# 1-Schematic_ISM_WAVER_V2.net
KiCad netlist of a schematic drawn in EasyEDA
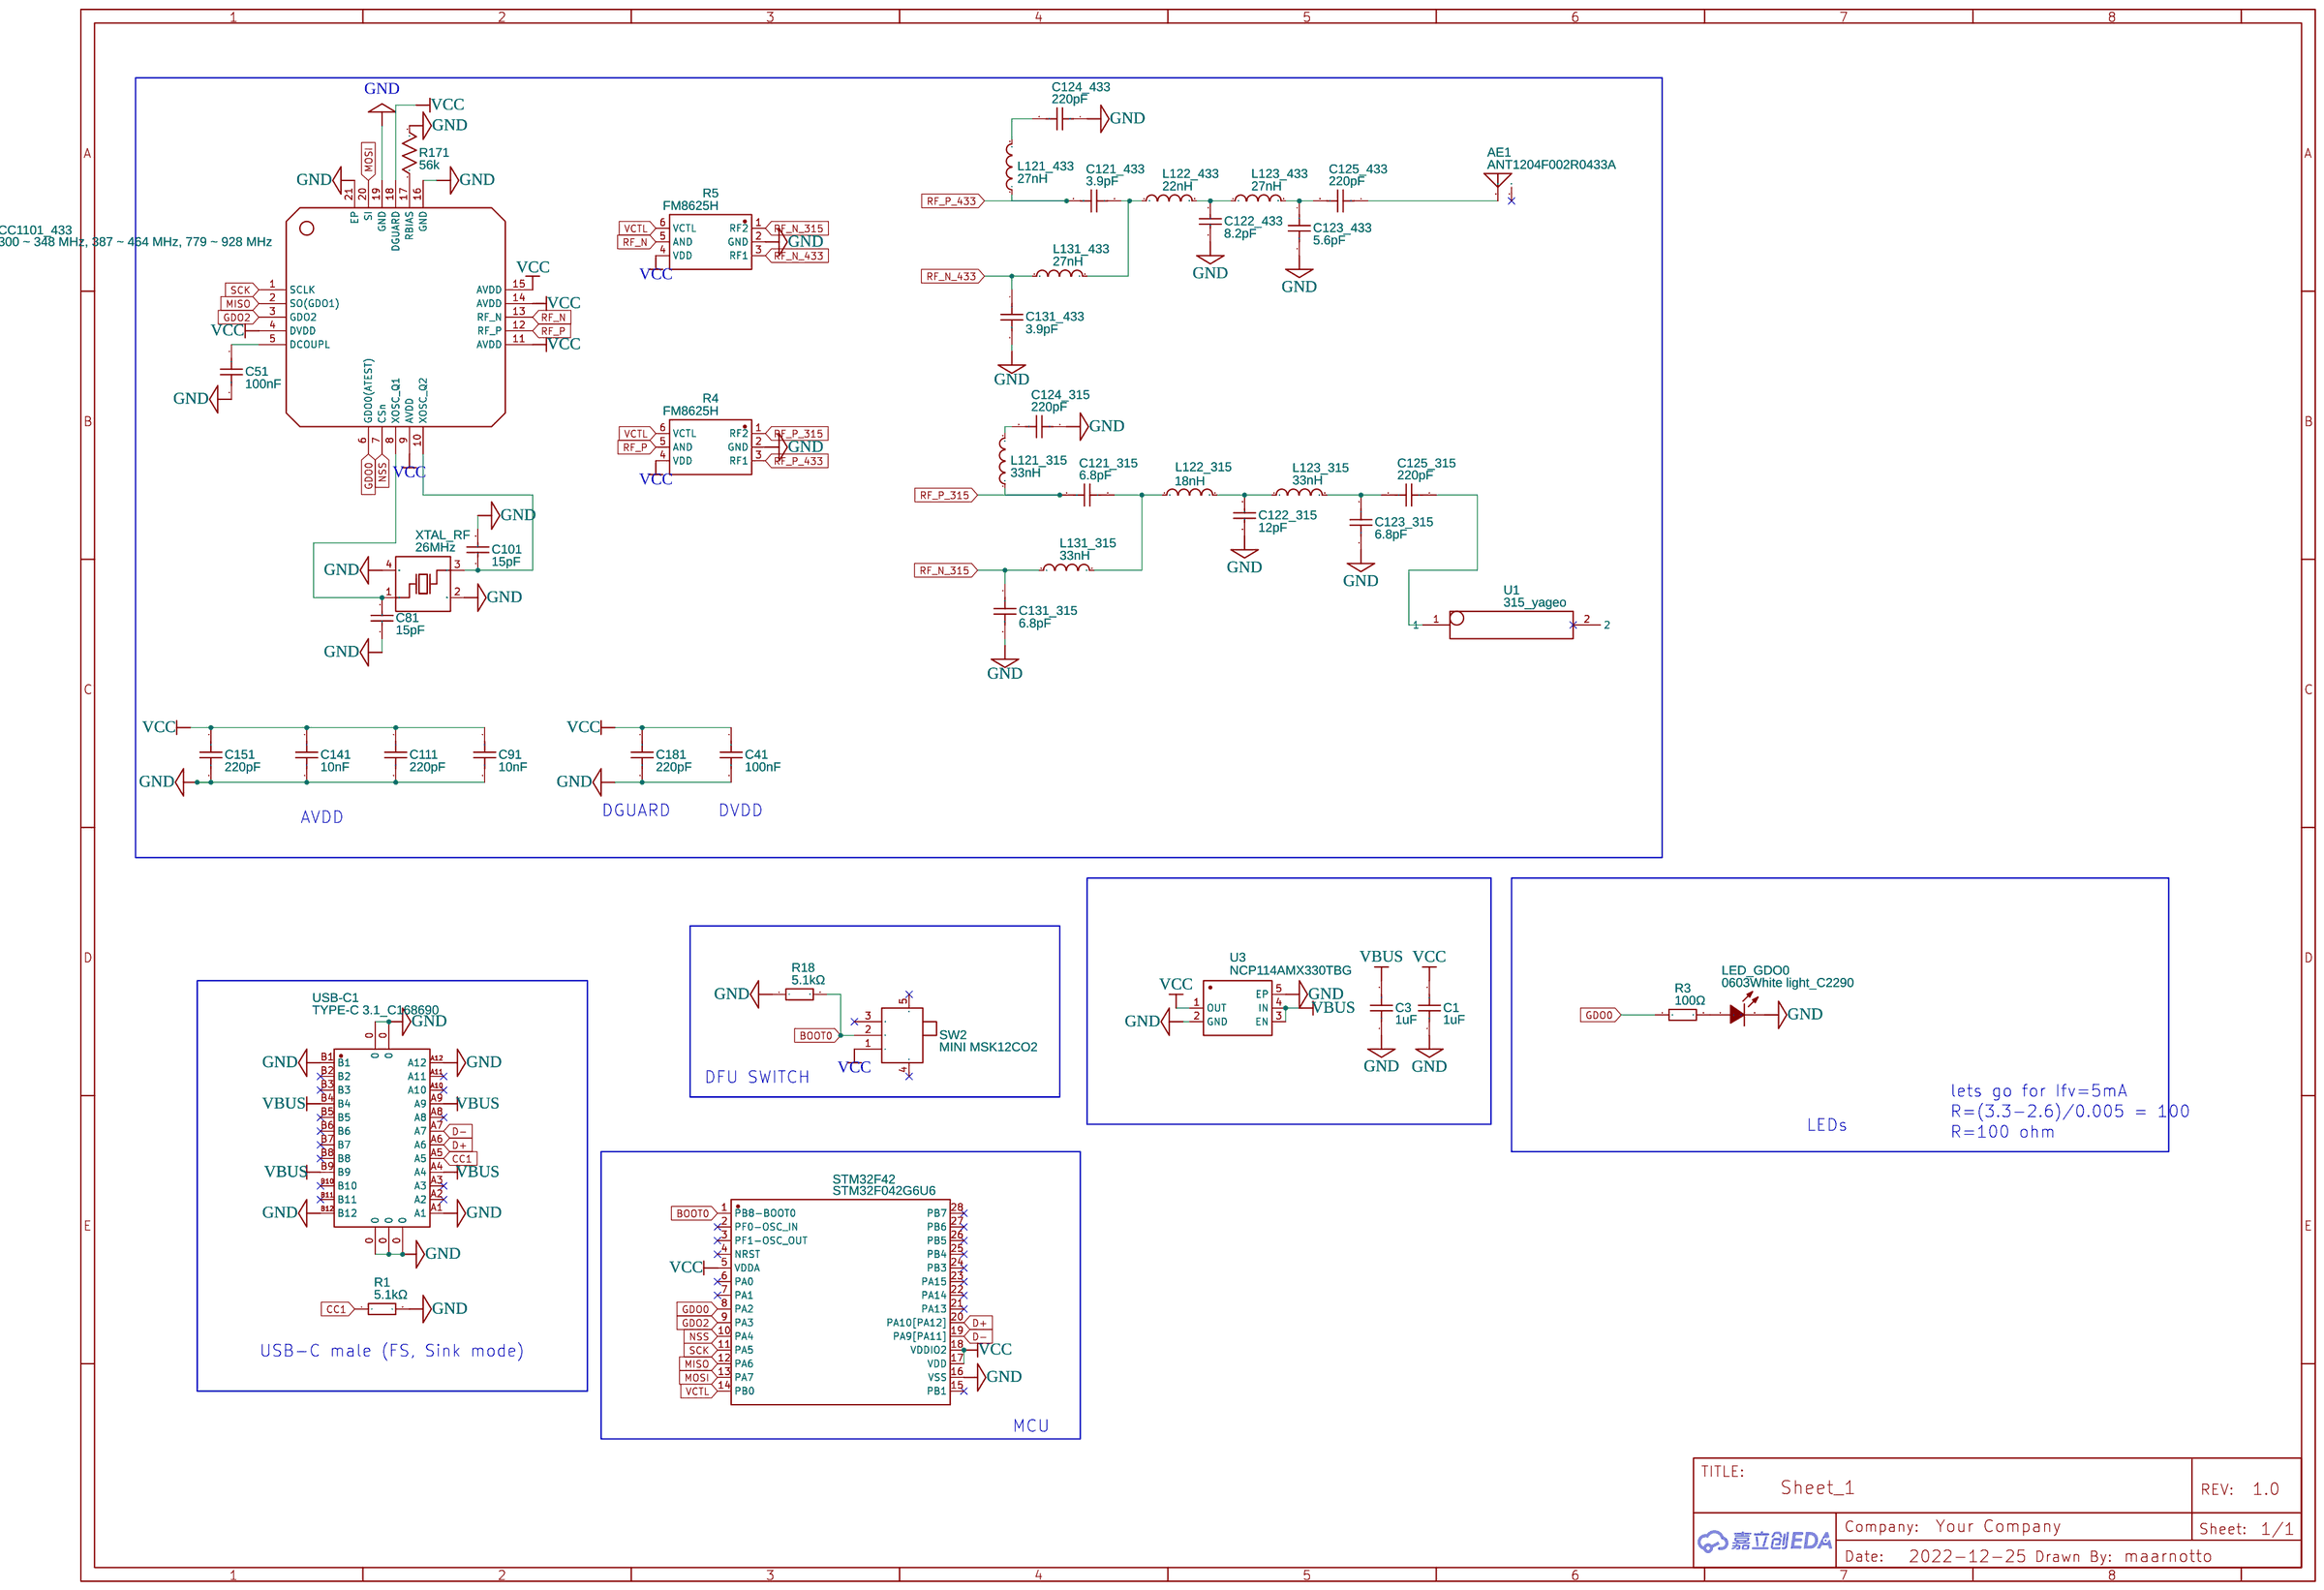
[diagram p0: schematic sheet]

(export (version "E")
  (design (tool "Eeschema 10.0.6"))
  (components
    (comp (ref "AE1")
      (value "ANT1204F002R0433A")
      (fields (field (name "Manufacturer") "YAGEO(国巨)"))
      (libsource (lib "") (part "ANT1204F002R0433A"))
    )
    (comp (ref "C1") (value "1uF") (libsource (lib "") (part "C_0603_US")))
    (comp (ref "C3") (value "1uF") (libsource (lib "") (part "C_0603_US")))
    (comp (ref "C41") (value "100nF") (libsource (lib "") (part "C_0402_US")))
    (comp (ref "C51") (value "100nF") (libsource (lib "") (part "C_0402_US")))
    (comp (ref "C81")
      (value "15pF")
      (fields (field (name "Manufacturer Part") "0402CG150J500NT") (field (name "Manufacturer") "FH(风华)"))
      (libsource (lib "") (part "0402CG150J500NT"))
    )
    (comp (ref "C91") (value "10nF") (libsource (lib "") (part "C_0402_US")))
    (comp (ref "C101")
      (value "15pF")
      (fields (field (name "Manufacturer Part") "0402CG150J500NT") (field (name "Manufacturer") "FH(风华)"))
      (libsource (lib "") (part "0402CG150J500NT"))
    )
    (comp (ref "C111") (value "220pF") (libsource (lib "") (part "C_0402_US")))
    (comp (ref "C121_315") (value "6.8pF") (libsource (lib "") (part "C_0402_US_4")))
    (comp (ref "C121_433") (value "3.9pF") (libsource (lib "") (part "C_0402_US_4")))
    (comp (ref "C122_315")
      (value "12pF")
      (fields (field (name "Manufacturer Part") "0402CG8R2C500NT") (field (name "Manufacturer") "FH(风华)"))
      (libsource (lib "") (part "0402CG8R2C500NT"))
    )
    (comp (ref "C122_433")
      (value "8.2pF")
      (fields (field (name "Manufacturer Part") "0402CG8R2C500NT") (field (name "Manufacturer") "FH(风华)"))
      (libsource (lib "") (part "0402CG8R2C500NT"))
    )
    (comp (ref "C123_315") (value "6.8pF") (libsource (lib "") (part "C_0402_US_2")))
    (comp (ref "C123_433") (value "5.6pF") (libsource (lib "") (part "C_0402_US_2")))
    (comp (ref "C124_315") (value "220pF") (libsource (lib "") (part "C_0402_US_5")))
    (comp (ref "C124_433") (value "220pF") (libsource (lib "") (part "C_0402_US_5")))
    (comp (ref "C125_315") (value "220pF") (libsource (lib "") (part "C_0402_US_3")))
    (comp (ref "C125_433") (value "220pF") (libsource (lib "") (part "C_0402_US_3")))
    (comp (ref "C131_315") (value "6.8pF") (libsource (lib "") (part "C_0402_US_1")))
    (comp (ref "C131_433") (value "3.9pF") (libsource (lib "") (part "C_0402_US_1")))
    (comp (ref "C141") (value "10nF") (libsource (lib "") (part "C_0402_US")))
    (comp (ref "C151") (value "220pF") (libsource (lib "") (part "C_0402_US")))
    (comp (ref "C181") (value "220pF") (libsource (lib "") (part "C_0402_US")))
    (comp (ref "CC1101_433")
      (value "300 ~ 348 MHz, 387 ~ 464 MHz, 779 ~ 928 MHz")
      (fields (field (name "Manufacturer Part") "CC1101RGPR") (field (name "Manufacturer") "TI(德州仪器)"))
      (libsource (lib "") (part "CC1101RGPR"))
    )
    (comp (ref "L121_315") (value "33nH") (libsource (lib "") (part "L0402_US_2")))
    (comp (ref "L121_433") (value "27nH") (libsource (lib "") (part "L0402_US_2")))
    (comp (ref "L122_315") (value "18nH") (libsource (lib "") (part "L0402_US_3")))
    (comp (ref "L122_433") (value "22nH") (libsource (lib "") (part "L0402_US_3")))
    (comp (ref "L123_315") (value "33nH") (libsource (lib "") (part "L0402_US_1")))
    (comp (ref "L123_433") (value "27nH") (libsource (lib "") (part "L0402_US_1")))
    (comp (ref "L131_315") (value "33nH") (libsource (lib "") (part "L0402_US")))
    (comp (ref "L131_433") (value "27nH") (libsource (lib "") (part "L0402_US")))
    (comp (ref "LED_GDO0")
      (value "0603White light_C2290")
      (fields (field (name "Manufacturer Part") "KT-0603白灯") (field (name "Manufacturer") "KENTO"))
      (libsource (lib "") (part "0603White light_C2290"))
    )
    (comp (ref "R1")
      (value "5.1kΩ")
      (fields
        (field (name "Manufacturer Part") "0402WGF5101TCE")
        (field (name "Manufacturer") "UNI-ROYAL(厚声)")
      )
      (libsource (lib "") (part "0402WGF5101TCE"))
    )
    (comp (ref "R3")
      (value "100Ω")
      (fields
        (field (name "Manufacturer Part") "0603WAF1000T5E")
        (field (name "Manufacturer") "UNI-ROYAL(厚声)")
      )
      (libsource (lib "") (part "0603WAF1000T5E"))
    )
    (comp (ref "R4")
      (value "FM8625H")
      (fields (field (name "Manufacturer") "FM(富满)"))
      (libsource (lib "") (part "FM8625H"))
    )
    (comp (ref "R5")
      (value "FM8625H")
      (fields (field (name "Manufacturer") "FM(富满)"))
      (libsource (lib "") (part "FM8625H"))
    )
    (comp (ref "R18")
      (value "5.1kΩ")
      (fields
        (field (name "Manufacturer Part") "0402WGF5101TCE")
        (field (name "Manufacturer") "UNI-ROYAL(厚声)")
      )
      (libsource (lib "") (part "0402WGF5101TCE"))
    )
    (comp (ref "R171") (value "56k") (libsource (lib "") (part "R_0402_US")))
    (comp (ref "STM32F42")
      (value "STM32F042G6U6")
      (fields (field (name "Manufacturer") "ST(意法半导体)"))
      (libsource (lib "") (part "STM32F042G6U6"))
    )
    (comp (ref "SW2")
      (value "MINI MSK12CO2")
      (fields (field (name "Manufacturer") "SHOU HAN(首韩)"))
      (libsource (lib "") (part "MINI MSK12CO2"))
    )
    (comp (ref "U1")
      (value "315_yageo")
      (fields
        (field (name "Manufacturer Part") "ANT1204F002R0315A")
        (field (name "Manufacturer") "PULSE ELECTRONICS")
      )
      (libsource (lib "") (part "315_yageo"))
    )
    (comp (ref "U3")
      (value "NCP114AMX330TBG")
      (fields (field (name "Manufacturer") "onsemi(安森美)"))
      (libsource (lib "") (part "NCP114AMX330TBG"))
    )
    (comp (ref "USB-C1")
      (value "TYPE-C 3.1_C168690")
      (fields (field (name "Manufacturer Part") "918-118A2021Y40000") (field (name "Manufacturer") "精拓金"))
      (libsource (lib "") (part "TYPE-C 3.1_C168690"))
    )
    (comp (ref "XTAL_RF")
      (value "26MHz")
      (fields (field (name "Manufacturer Part") "TAXM26M4RDBCCT2T") (field (name "Manufacturer") "YJX(雅晶鑫)"))
      (libsource (lib "") (part "SMD-3225_4P26MHZ10PF10PPM-40&#126;+85℃"))
    )
  )
  (nets
    (net (code "1") (name "BOOT0") (class "Default")
      (node (ref "R18") (pin "2") (pinfunction "2_2") (pintype "input"))
      (node (ref "STM32F42") (pin "1") (pinfunction "PB8-BOOT0_1") (pintype "unspecified"))
      (node (ref "SW2") (pin "2") (pinfunction "2_2") (pintype "unspecified"))
    )
    (net (code "2") (name "CC1") (class "Default")
      (node (ref "R1") (pin "1") (pinfunction "1_1") (pintype "input"))
      (node (ref "USB-C1") (pin "A5") (pinfunction "A5_A5") (pintype "unspecified"))
    )
    (net (code "3") (name "D+") (class "Default")
      (node (ref "STM32F42") (pin "20") (pinfunction "PA10[PA12]_20") (pintype "unspecified"))
      (node (ref "USB-C1") (pin "A6") (pinfunction "A6_A6") (pintype "unspecified"))
    )
    (net (code "4") (name "D-") (class "Default")
      (node (ref "STM32F42") (pin "19") (pinfunction "PA9[PA11]_19") (pintype "unspecified"))
      (node (ref "USB-C1") (pin "A7") (pinfunction "A7_A7") (pintype "unspecified"))
    )
    (net (code "5") (name "GDO0") (class "Default")
      (node (ref "CC1101_433") (pin "6") (pinfunction "GDO0(ATEST)_6") (pintype "unspecified"))
      (node (ref "R3") (pin "1") (pinfunction "1_1") (pintype "input"))
      (node (ref "STM32F42") (pin "8") (pinfunction "PA2_8") (pintype "unspecified"))
    )
    (net (code "6") (name "GDO2") (class "Default")
      (node (ref "CC1101_433") (pin "3") (pinfunction "GDO2_3") (pintype "unspecified"))
      (node (ref "STM32F42") (pin "9") (pinfunction "PA3_9") (pintype "unspecified"))
    )
    (net (code "7") (name "GND") (class "Default")
      (node (ref "C1") (pin "1") (pinfunction "1_1") (pintype "unspecified"))
      (node (ref "C101") (pin "2") (pinfunction "2_2") (pintype "input"))
      (node (ref "C111") (pin "2") (pinfunction "2_2") (pintype "unspecified"))
      (node (ref "C122_315") (pin "1") (pinfunction "1_1") (pintype "input"))
      (node (ref "C122_433") (pin "1") (pinfunction "1_1") (pintype "input"))
      (node (ref "C123_315") (pin "2") (pinfunction "2_2") (pintype "unspecified"))
      (node (ref "C123_433") (pin "2") (pinfunction "2_2") (pintype "unspecified"))
      (node (ref "C124_315") (pin "1") (pinfunction "1_1") (pintype "unspecified"))
      (node (ref "C124_433") (pin "1") (pinfunction "1_1") (pintype "unspecified"))
      (node (ref "C131_315") (pin "2") (pinfunction "2_2") (pintype "unspecified"))
      (node (ref "C131_433") (pin "2") (pinfunction "2_2") (pintype "unspecified"))
      (node (ref "C141") (pin "2") (pinfunction "2_2") (pintype "unspecified"))
      (node (ref "C151") (pin "2") (pinfunction "2_2") (pintype "unspecified"))
      (node (ref "C181") (pin "2") (pinfunction "2_2") (pintype "unspecified"))
      (node (ref "C3") (pin "1") (pinfunction "1_1") (pintype "unspecified"))
      (node (ref "C41") (pin "2") (pinfunction "2_2") (pintype "unspecified"))
      (node (ref "C51") (pin "2") (pinfunction "2_2") (pintype "unspecified"))
      (node (ref "C81") (pin "1") (pinfunction "1_1") (pintype "input"))
      (node (ref "C91") (pin "2") (pinfunction "2_2") (pintype "unspecified"))
      (node (ref "CC1101_433") (pin "16") (pinfunction "GND_16") (pintype "unspecified"))
      (node (ref "CC1101_433") (pin "19") (pinfunction "GND_19") (pintype "unspecified"))
      (node (ref "CC1101_433") (pin "21") (pinfunction "EP_21") (pintype "unspecified"))
      (node (ref "LED_GDO0") (pin "2") (pinfunction "K_2") (pintype "unspecified"))
      (node (ref "R1") (pin "2") (pinfunction "2_2") (pintype "input"))
      (node (ref "R171") (pin "2") (pinfunction "2_2") (pintype "unspecified"))
      (node (ref "R18") (pin "1") (pinfunction "1_1") (pintype "input"))
      (node (ref "R4") (pin "2") (pinfunction "GND_2") (pintype "unspecified"))
      (node (ref "R5") (pin "2") (pinfunction "GND_2") (pintype "unspecified"))
      (node (ref "STM32F42") (pin "16") (pinfunction "VSS_16") (pintype "unspecified"))
      (node (ref "U3") (pin "2") (pinfunction "GND_2") (pintype "unspecified"))
      (node (ref "U3") (pin "5") (pinfunction "EP_5") (pintype "unspecified"))
      (node (ref "USB-C1") (pin "0") (pinfunction "0_0") (pintype "unspecified"))
      (node (ref "USB-C1") (pin "A1") (pinfunction "A1_A1") (pintype "unspecified"))
      (node (ref "USB-C1") (pin "A12") (pinfunction "A12_A12") (pintype "unspecified"))
      (node (ref "USB-C1") (pin "B1") (pinfunction "B1_B1") (pintype "unspecified"))
      (node (ref "USB-C1") (pin "B12") (pinfunction "B12_B12") (pintype "unspecified"))
      (node (ref "XTAL_RF") (pin "2") (pinfunction "GND_2") (pintype "unspecified"))
      (node (ref "XTAL_RF") (pin "4") (pinfunction "GND_4") (pintype "unspecified"))
    )
    (net (code "8") (name "MISO") (class "Default")
      (node (ref "CC1101_433") (pin "2") (pinfunction "SO(GDO1)_2") (pintype "unspecified"))
      (node (ref "STM32F42") (pin "12") (pinfunction "PA6_12") (pintype "unspecified"))
    )
    (net (code "9") (name "MOSI") (class "Default")
      (node (ref "CC1101_433") (pin "20") (pinfunction "SI_20") (pintype "unspecified"))
      (node (ref "STM32F42") (pin "13") (pinfunction "PA7_13") (pintype "unspecified"))
    )
    (net (code "10") (name "NSS") (class "Default")
      (node (ref "CC1101_433") (pin "7") (pinfunction "CSn_7") (pintype "unspecified"))
      (node (ref "STM32F42") (pin "10") (pinfunction "PA4_10") (pintype "unspecified"))
    )
    (net (code "11") (name "Net-(AE1-PadS1)") (class "Default")
      (node (ref "AE1") (pin "S1") (pinfunction "S1_S1") (pintype "unspecified"))
      (node (ref "C125_433") (pin "1") (pinfunction "1_1") (pintype "unspecified"))
    )
    (net (code "12") (name "Net-(C121_315-Pad1)") (class "Default")
      (node (ref "C121_315") (pin "1") (pinfunction "1_1") (pintype "unspecified"))
      (node (ref "L122_315") (pin "1") (pinfunction "1_1") (pintype "unspecified"))
      (node (ref "L131_315") (pin "2") (pinfunction "2_2") (pintype "unspecified"))
    )
    (net (code "13") (name "Net-(C121_433-Pad1)") (class "Default")
      (node (ref "C121_433") (pin "1") (pinfunction "1_1") (pintype "unspecified"))
      (node (ref "L122_433") (pin "1") (pinfunction "1_1") (pintype "unspecified"))
      (node (ref "L131_433") (pin "2") (pinfunction "2_2") (pintype "unspecified"))
    )
    (net (code "14") (name "Net-(C122_315-Pad2)") (class "Default")
      (node (ref "C122_315") (pin "2") (pinfunction "2_2") (pintype "input"))
      (node (ref "L122_315") (pin "2") (pinfunction "2_2") (pintype "unspecified"))
      (node (ref "L123_315") (pin "1") (pinfunction "1_1") (pintype "unspecified"))
    )
    (net (code "15") (name "Net-(C122_433-Pad2)") (class "Default")
      (node (ref "C122_433") (pin "2") (pinfunction "2_2") (pintype "input"))
      (node (ref "L122_433") (pin "2") (pinfunction "2_2") (pintype "unspecified"))
      (node (ref "L123_433") (pin "1") (pinfunction "1_1") (pintype "unspecified"))
    )
    (net (code "16") (name "Net-(C123_315-Pad1)") (class "Default")
      (node (ref "C123_315") (pin "1") (pinfunction "1_1") (pintype "unspecified"))
      (node (ref "C125_315") (pin "2") (pinfunction "2_2") (pintype "unspecified"))
      (node (ref "L123_315") (pin "2") (pinfunction "2_2") (pintype "unspecified"))
    )
    (net (code "17") (name "Net-(C123_433-Pad1)") (class "Default")
      (node (ref "C123_433") (pin "1") (pinfunction "1_1") (pintype "unspecified"))
      (node (ref "C125_433") (pin "2") (pinfunction "2_2") (pintype "unspecified"))
      (node (ref "L123_433") (pin "2") (pinfunction "2_2") (pintype "unspecified"))
    )
    (net (code "18") (name "Net-(C124_315-Pad2)") (class "Default")
      (node (ref "C124_315") (pin "2") (pinfunction "2_2") (pintype "unspecified"))
      (node (ref "L121_315") (pin "2") (pinfunction "2_2") (pintype "unspecified"))
    )
    (net (code "19") (name "Net-(C124_433-Pad2)") (class "Default")
      (node (ref "C124_433") (pin "2") (pinfunction "2_2") (pintype "unspecified"))
      (node (ref "L121_433") (pin "2") (pinfunction "2_2") (pintype "unspecified"))
    )
    (net (code "20") (name "Net-(C125_315-Pad1)") (class "Default")
      (node (ref "C125_315") (pin "1") (pinfunction "1_1") (pintype "unspecified"))
      (node (ref "U1") (pin "1") (pinfunction "1_1") (pintype "unspecified"))
    )
    (net (code "21") (name "Net-(CC1101_433-DCOUPL)") (class "Default")
      (node (ref "C51") (pin "1") (pinfunction "1_1") (pintype "unspecified"))
      (node (ref "CC1101_433") (pin "5") (pinfunction "DCOUPL_5") (pintype "unspecified"))
    )
    (net (code "22") (name "Net-(CC1101_433-RBIAS)") (class "Default")
      (node (ref "CC1101_433") (pin "17") (pinfunction "RBIAS_17") (pintype "unspecified"))
      (node (ref "R171") (pin "1") (pinfunction "1_1") (pintype "unspecified"))
    )
    (net (code "23") (name "Net-(CC1101_433-XOSC_Q1)") (class "Default")
      (node (ref "C81") (pin "2") (pinfunction "2_2") (pintype "input"))
      (node (ref "CC1101_433") (pin "8") (pinfunction "XOSC_Q1_8") (pintype "unspecified"))
      (node (ref "XTAL_RF") (pin "1") (pinfunction "OSC1_1") (pintype "unspecified"))
    )
    (net (code "24") (name "Net-(CC1101_433-XOSC_Q2)") (class "Default")
      (node (ref "C101") (pin "1") (pinfunction "1_1") (pintype "input"))
      (node (ref "CC1101_433") (pin "10") (pinfunction "XOSC_Q2_10") (pintype "unspecified"))
      (node (ref "XTAL_RF") (pin "3") (pinfunction "OSC2_3") (pintype "unspecified"))
    )
    (net (code "25") (name "Net-(LED_GDO0-A)") (class "Default")
      (node (ref "LED_GDO0") (pin "1") (pinfunction "A_1") (pintype "unspecified"))
      (node (ref "R3") (pin "2") (pinfunction "2_2") (pintype "input"))
    )
    (net (code "26") (name "RF_N") (class "Default")
      (node (ref "CC1101_433") (pin "13") (pinfunction "RF_N_13") (pintype "unspecified"))
      (node (ref "R5") (pin "5") (pinfunction "AND_5") (pintype "unspecified"))
    )
    (net (code "27") (name "RF_N_315") (class "Default")
      (node (ref "C131_315") (pin "1") (pinfunction "1_1") (pintype "unspecified"))
      (node (ref "L131_315") (pin "1") (pinfunction "1_1") (pintype "unspecified"))
      (node (ref "R5") (pin "1") (pinfunction "RF2_1") (pintype "unspecified"))
    )
    (net (code "28") (name "RF_N_433") (class "Default")
      (node (ref "C131_433") (pin "1") (pinfunction "1_1") (pintype "unspecified"))
      (node (ref "L131_433") (pin "1") (pinfunction "1_1") (pintype "unspecified"))
      (node (ref "R5") (pin "3") (pinfunction "RF1_3") (pintype "unspecified"))
    )
    (net (code "29") (name "RF_P") (class "Default")
      (node (ref "CC1101_433") (pin "12") (pinfunction "RF_P_12") (pintype "unspecified"))
      (node (ref "R4") (pin "5") (pinfunction "AND_5") (pintype "unspecified"))
    )
    (net (code "30") (name "RF_P_315") (class "Default")
      (node (ref "C121_315") (pin "2") (pinfunction "2_2") (pintype "unspecified"))
      (node (ref "L121_315") (pin "1") (pinfunction "1_1") (pintype "unspecified"))
      (node (ref "R4") (pin "1") (pinfunction "RF2_1") (pintype "unspecified"))
    )
    (net (code "31") (name "RF_P_433") (class "Default")
      (node (ref "C121_433") (pin "2") (pinfunction "2_2") (pintype "unspecified"))
      (node (ref "L121_433") (pin "1") (pinfunction "1_1") (pintype "unspecified"))
      (node (ref "R4") (pin "3") (pinfunction "RF1_3") (pintype "unspecified"))
    )
    (net (code "32") (name "SCK") (class "Default")
      (node (ref "CC1101_433") (pin "1") (pinfunction "SCLK_1") (pintype "unspecified"))
      (node (ref "STM32F42") (pin "11") (pinfunction "PA5_11") (pintype "unspecified"))
    )
    (net (code "33") (name "VBUS") (class "Default")
      (node (ref "C3") (pin "2") (pinfunction "2_2") (pintype "unspecified"))
      (node (ref "U3") (pin "3") (pinfunction "EN_3") (pintype "unspecified"))
      (node (ref "U3") (pin "4") (pinfunction "IN_4") (pintype "unspecified"))
      (node (ref "USB-C1") (pin "A4") (pinfunction "A4_A4") (pintype "unspecified"))
      (node (ref "USB-C1") (pin "A9") (pinfunction "A9_A9") (pintype "unspecified"))
      (node (ref "USB-C1") (pin "B4") (pinfunction "B4_B4") (pintype "unspecified"))
      (node (ref "USB-C1") (pin "B9") (pinfunction "B9_B9") (pintype "unspecified"))
    )
    (net (code "34") (name "VCC") (class "Default")
      (node (ref "C1") (pin "2") (pinfunction "2_2") (pintype "unspecified"))
      (node (ref "C111") (pin "1") (pinfunction "1_1") (pintype "unspecified"))
      (node (ref "C141") (pin "1") (pinfunction "1_1") (pintype "unspecified"))
      (node (ref "C151") (pin "1") (pinfunction "1_1") (pintype "unspecified"))
      (node (ref "C181") (pin "1") (pinfunction "1_1") (pintype "unspecified"))
      (node (ref "C41") (pin "1") (pinfunction "1_1") (pintype "unspecified"))
      (node (ref "C91") (pin "1") (pinfunction "1_1") (pintype "unspecified"))
      (node (ref "CC1101_433") (pin "11") (pinfunction "AVDD_11") (pintype "unspecified"))
      (node (ref "CC1101_433") (pin "14") (pinfunction "AVDD_14") (pintype "unspecified"))
      (node (ref "CC1101_433") (pin "15") (pinfunction "AVDD_15") (pintype "unspecified"))
      (node (ref "CC1101_433") (pin "18") (pinfunction "DGUARD_18") (pintype "unspecified"))
      (node (ref "CC1101_433") (pin "4") (pinfunction "DVDD_4") (pintype "unspecified"))
      (node (ref "CC1101_433") (pin "9") (pinfunction "AVDD_9") (pintype "unspecified"))
      (node (ref "R4") (pin "4") (pinfunction "VDD_4") (pintype "unspecified"))
      (node (ref "R5") (pin "4") (pinfunction "VDD_4") (pintype "unspecified"))
      (node (ref "STM32F42") (pin "17") (pinfunction "VDD_17") (pintype "unspecified"))
      (node (ref "STM32F42") (pin "18") (pinfunction "VDDIO2_18") (pintype "unspecified"))
      (node (ref "STM32F42") (pin "5") (pinfunction "VDDA_5") (pintype "unspecified"))
      (node (ref "SW2") (pin "1") (pinfunction "1_1") (pintype "unspecified"))
      (node (ref "U3") (pin "1") (pinfunction "OUT_1") (pintype "unspecified"))
    )
    (net (code "35") (name "VCTL") (class "Default")
      (node (ref "R4") (pin "6") (pinfunction "VCTL_6") (pintype "unspecified"))
      (node (ref "R5") (pin "6") (pinfunction "VCTL_6") (pintype "unspecified"))
      (node (ref "STM32F42") (pin "14") (pinfunction "PB0_14") (pintype "unspecified"))
    )
    (net (code "36") (name "unconnected-(AE1-PadS2)") (class "Default")
      (node (ref "AE1") (pin "S2") (pinfunction "S2_S2") (pintype "unspecified+no_connect"))
    )
    (net (code "37") (name "unconnected-(STM32F42-NRST-Pad4)") (class "Default")
      (node (ref "STM32F42") (pin "4") (pinfunction "NRST_4") (pintype "unspecified+no_connect"))
    )
    (net (code "38") (name "unconnected-(STM32F42-PA0-Pad6)") (class "Default")
      (node (ref "STM32F42") (pin "6") (pinfunction "PA0_6") (pintype "unspecified+no_connect"))
    )
    (net (code "39") (name "unconnected-(STM32F42-PA1-Pad7)") (class "Default")
      (node (ref "STM32F42") (pin "7") (pinfunction "PA1_7") (pintype "unspecified+no_connect"))
    )
    (net (code "40") (name "unconnected-(STM32F42-PA13-Pad21)") (class "Default")
      (node (ref "STM32F42") (pin "21") (pinfunction "PA13_21") (pintype "unspecified+no_connect"))
    )
    (net (code "41") (name "unconnected-(STM32F42-PA14-Pad22)") (class "Default")
      (node (ref "STM32F42") (pin "22") (pinfunction "PA14_22") (pintype "unspecified+no_connect"))
    )
    (net (code "42") (name "unconnected-(STM32F42-PA15-Pad23)") (class "Default")
      (node (ref "STM32F42") (pin "23") (pinfunction "PA15_23") (pintype "unspecified+no_connect"))
    )
    (net (code "43") (name "unconnected-(STM32F42-PB1-Pad15)") (class "Default")
      (node (ref "STM32F42") (pin "15") (pinfunction "PB1_15") (pintype "unspecified+no_connect"))
    )
    (net (code "44") (name "unconnected-(STM32F42-PB3-Pad24)") (class "Default")
      (node (ref "STM32F42") (pin "24") (pinfunction "PB3_24") (pintype "unspecified+no_connect"))
    )
    (net (code "45") (name "unconnected-(STM32F42-PB4-Pad25)") (class "Default")
      (node (ref "STM32F42") (pin "25") (pinfunction "PB4_25") (pintype "unspecified+no_connect"))
    )
    (net (code "46") (name "unconnected-(STM32F42-PB5-Pad26)") (class "Default")
      (node (ref "STM32F42") (pin "26") (pinfunction "PB5_26") (pintype "unspecified+no_connect"))
    )
    (net (code "47") (name "unconnected-(STM32F42-PB6-Pad27)") (class "Default")
      (node (ref "STM32F42") (pin "27") (pinfunction "PB6_27") (pintype "unspecified+no_connect"))
    )
    (net (code "48") (name "unconnected-(STM32F42-PB7-Pad28)") (class "Default")
      (node (ref "STM32F42") (pin "28") (pinfunction "PB7_28") (pintype "unspecified+no_connect"))
    )
    (net (code "49") (name "unconnected-(STM32F42-PF0-OSC_IN-Pad2)") (class "Default")
      (node (ref "STM32F42") (pin "2") (pinfunction "PF0-OSC_IN_2") (pintype "unspecified+no_connect"))
    )
    (net (code "50") (name "unconnected-(STM32F42-PF1-OSC_OUT-Pad3)") (class "Default")
      (node (ref "STM32F42") (pin "3") (pinfunction "PF1-OSC_OUT_3") (pintype "unspecified+no_connect"))
    )
    (net (code "51") (name "unconnected-(SW2-Pad3)") (class "Default")
      (node (ref "SW2") (pin "3") (pinfunction "3_3") (pintype "unspecified+no_connect"))
    )
    (net (code "52") (name "unconnected-(SW2-Pad4)") (class "Default")
      (node (ref "SW2") (pin "4") (pinfunction "4_4") (pintype "unspecified+no_connect"))
    )
    (net (code "53") (name "unconnected-(SW2-Pad5)") (class "Default")
      (node (ref "SW2") (pin "5") (pinfunction "5_5") (pintype "unspecified+no_connect"))
    )
    (net (code "54") (name "unconnected-(U1-Pad2)") (class "Default")
      (node (ref "U1") (pin "2") (pinfunction "2_2") (pintype "unspecified+no_connect"))
    )
    (net (code "55") (name "unconnected-(USB-C1-PadA2)") (class "Default")
      (node (ref "USB-C1") (pin "A2") (pinfunction "A2_A2") (pintype "unspecified+no_connect"))
    )
    (net (code "56") (name "unconnected-(USB-C1-PadA3)") (class "Default")
      (node (ref "USB-C1") (pin "A3") (pinfunction "A3_A3") (pintype "unspecified+no_connect"))
    )
    (net (code "57") (name "unconnected-(USB-C1-PadA8)") (class "Default")
      (node (ref "USB-C1") (pin "A8") (pinfunction "A8_A8") (pintype "unspecified+no_connect"))
    )
    (net (code "58") (name "unconnected-(USB-C1-PadA10)") (class "Default")
      (node (ref "USB-C1") (pin "A10") (pinfunction "A10_A10") (pintype "unspecified+no_connect"))
    )
    (net (code "59") (name "unconnected-(USB-C1-PadA11)") (class "Default")
      (node (ref "USB-C1") (pin "A11") (pinfunction "A11_A11") (pintype "unspecified+no_connect"))
    )
    (net (code "60") (name "unconnected-(USB-C1-PadB2)") (class "Default")
      (node (ref "USB-C1") (pin "B2") (pinfunction "B2_B2") (pintype "unspecified+no_connect"))
    )
    (net (code "61") (name "unconnected-(USB-C1-PadB3)") (class "Default")
      (node (ref "USB-C1") (pin "B3") (pinfunction "B3_B3") (pintype "unspecified+no_connect"))
    )
    (net (code "62") (name "unconnected-(USB-C1-PadB5)") (class "Default")
      (node (ref "USB-C1") (pin "B5") (pinfunction "B5_B5") (pintype "unspecified+no_connect"))
    )
    (net (code "63") (name "unconnected-(USB-C1-PadB6)") (class "Default")
      (node (ref "USB-C1") (pin "B6") (pinfunction "B6_B6") (pintype "unspecified+no_connect"))
    )
    (net (code "64") (name "unconnected-(USB-C1-PadB7)") (class "Default")
      (node (ref "USB-C1") (pin "B7") (pinfunction "B7_B7") (pintype "unspecified+no_connect"))
    )
    (net (code "65") (name "unconnected-(USB-C1-PadB8)") (class "Default")
      (node (ref "USB-C1") (pin "B8") (pinfunction "B8_B8") (pintype "unspecified+no_connect"))
    )
    (net (code "66") (name "unconnected-(USB-C1-PadB10)") (class "Default")
      (node (ref "USB-C1") (pin "B10") (pinfunction "B10_B10") (pintype "unspecified+no_connect"))
    )
    (net (code "67") (name "unconnected-(USB-C1-PadB11)") (class "Default")
      (node (ref "USB-C1") (pin "B11") (pinfunction "B11_B11") (pintype "unspecified+no_connect"))
    )
  )
)
